# bus_filter.net
KiCad netlist of a schematic drawn in Altium Designer
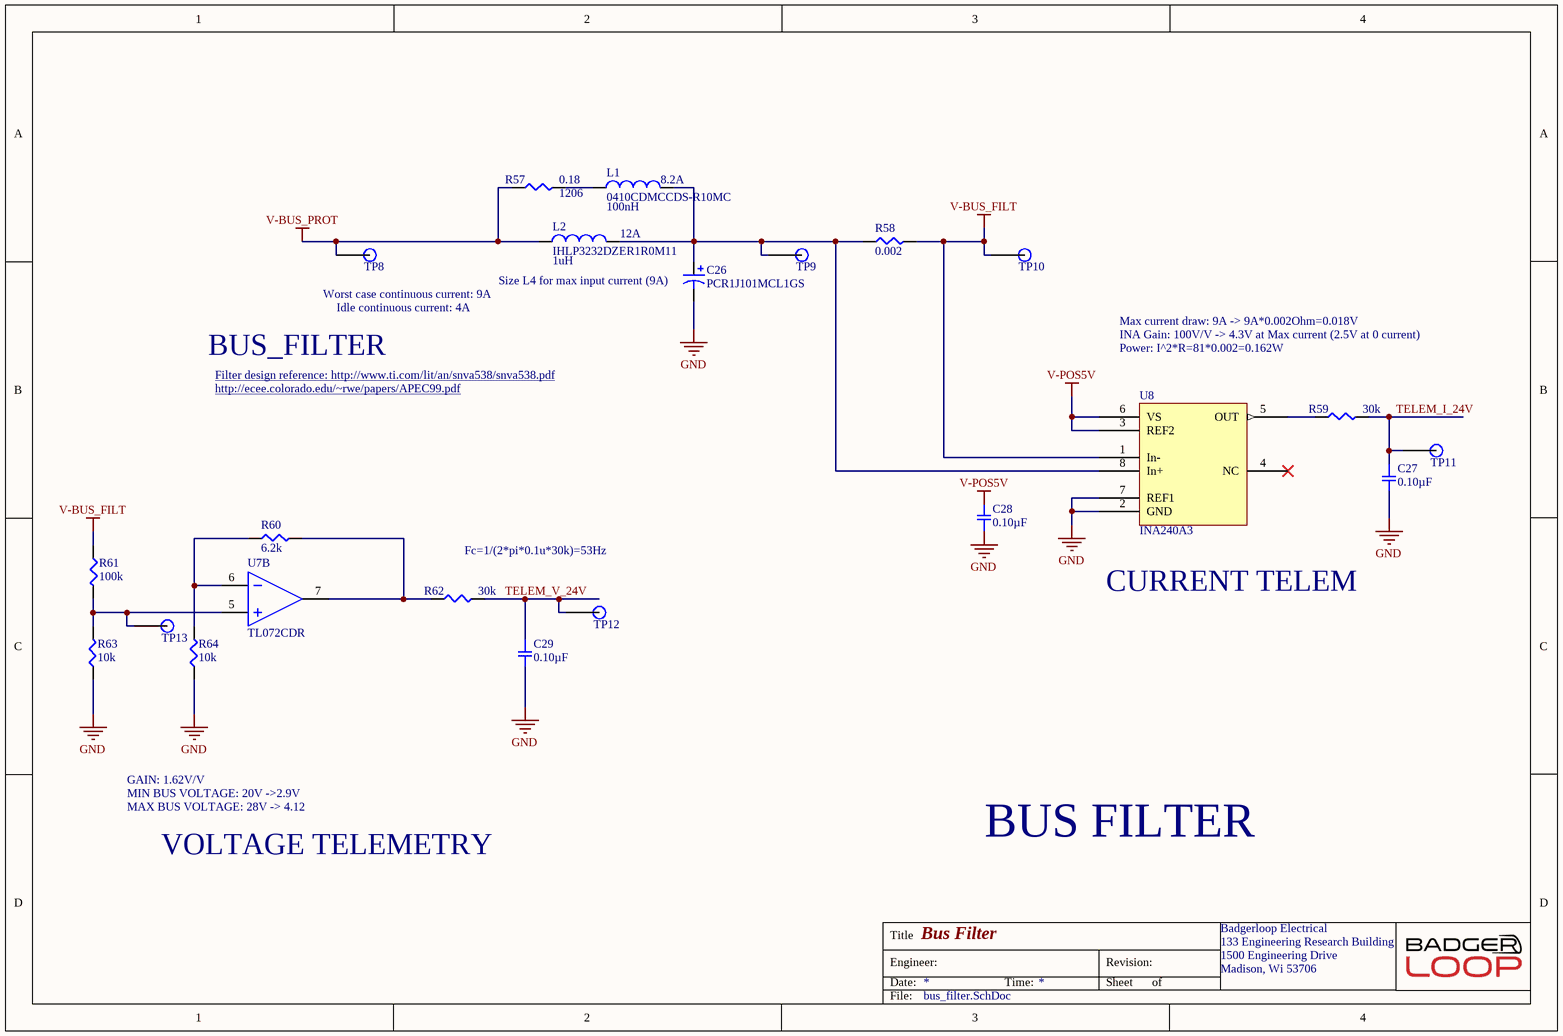
[diagram p0: bus_filter.SchDoc]

(export (version "E")
  (design (tool "Eeschema 10.0.6"))
  (components
    (comp (ref "C26")
      (value "PCR1J101MCL1GS")
      (footprint "CAPAE110103X126M")
      (description "CAP ALUM POLY 100UF 20% 63V SMD")
      (fields (field (name "MANUFACTURER") "Nichicon") (field (name "TOLERANCE") "20%"))
      (libsource (lib "capacitors") (part "PCR1J101MCL1GS"))
    )
    (comp (ref "C27")
      (value "0.10µF")
      (footprint "SMD-0805C")
      (description "CAP CER 0.1UF 16V X7R 0805")
      (fields
        (field (name "DIGI-KEY PART NUMBER") "490-1683-1-ND")
        (field (name "PART NUMBER") "GRM219R71C104KA01D")
      )
      (libsource (lib "capacitors") (part "GRM219R71C104KA01D"))
    )
    (comp (ref "C28")
      (value "0.10µF")
      (footprint "SMD-0805C")
      (description "CAP CER 0.1UF 10V U2J 0805")
      (fields
        (field (name "DIGI-KEY PART NUMBER") "490-11592-1-ND")
        (field (name "PART NUMBER") "GRM21B7U1A104JA01L")
      )
      (libsource (lib "capacitors") (part "GRM21B7U1A104JA01L"))
    )
    (comp (ref "C29")
      (value "0.10µF")
      (footprint "SMD-0805C")
      (description "CAP CER 0.1UF 16V X7R 0805")
      (fields
        (field (name "DIGI-KEY PART NUMBER") "490-1683-1-ND")
        (field (name "PART NUMBER") "GRM219R71C104KA01D")
      )
      (libsource (lib "capacitors") (part "GRM219R71C104KA01D"))
    )
    (comp (ref "L1")
      (value "0410CDMCCDS-R10MC")
      (footprint "INDM4442X20N")
      (fields
        (field (name "MANUFACTURER") "Sumida")
        (field (name "INDUCTANCE") "100nH")
        (field (name "SATURATION CURRENT") "8.2A")
      )
      (libsource (lib "inductor") (part "0410CDMCCDS-R10MC"))
    )
    (comp (ref "L2")
      (value "IHLP3232DZER1R0M11")
      (footprint "INDM8682X40N")
      (description "Fixed Inductors 1uH 20% Low Profile")
      (fields
        (field (name "MANUFACTURER") "Vishay Dale")
        (field (name "TOLERANCE") "20%")
        (field (name "SATURATION CURRENT") "12A")
        (field (name "INDUCTANCE") "1uH")
      )
      (libsource (lib "misc") (part "IHLP3232DZER1R0M11"))
    )
    (comp (ref "R57")
      (value "0.18")
      (footprint "SMD-1206-RES")
      (description "RES SMD 0.18 OHM 1% 1/2W 1206")
      (fields
        (field (name "PART NUMBER") "ERJ-8BSFR18V")
        (field (name "DIGI-KEY PART NUMBER") "P17683CT-ND")
        (field (name "SUPPLIER DEVICE PACKAGE") "1206")
      )
      (libsource (lib "resistors") (part "ERJ-8BSFR18V"))
    )
    (comp (ref "R58")
      (value "0.002")
      (footprint "SMD-1206-RES")
      (description "RES SMD 0.002 OHM 1% 1W 1206")
      (fields
        (field (name "PART NUMBER") "ERJ-MP2MF2M0U")
        (field (name "DIGI-KEY PART NUMBER") "P19341CT-ND")
      )
      (libsource (lib "resistors") (part "ERJ-MP2MF2M0U"))
    )
    (comp (ref "R59")
      (value "30k")
      (footprint "SMD-0805-RES")
      (description "RES SMD 30K OHM 1% 1/8W 0805")
      (fields
        (field (name "PART NUMBER") "ERJ-6ENF3002V")
        (field (name "DIGI-KEY PART NUMBER") "P30.0KCCT-ND")
      )
      (libsource (lib "resistors") (part "ERJ-6ENF3002V"))
    )
    (comp (ref "R60")
      (value "6.2k")
      (footprint "SMD-0805-RES")
      (description "RES SMD 6.2K OHM 5% 1/2W 0805")
      (fields
        (field (name "PART NUMBER") "ERJ-P06J622V")
        (field (name "DIGI-KEY PART NUMBER") "P6.2KADCT-ND")
      )
      (libsource (lib "resistors") (part "ERJ-P06J622V"))
    )
    (comp (ref "R61")
      (value "100k")
      (footprint "SMD-0805-RES")
      (description "RES SMD 100K OHM 5% 1/2W 0805")
      (fields
        (field (name "PART NUMBER") "ERJ-P06J104V")
        (field (name "DIGI-KEY PART NUMBER") "P100KADCT-ND")
      )
      (libsource (lib "resistors") (part "ERJ-P06J104V"))
    )
    (comp (ref "R62")
      (value "30k")
      (footprint "SMD-0805-RES")
      (description "RES SMD 30K OHM 1% 1/8W 0805")
      (fields
        (field (name "PART NUMBER") "ERJ-6ENF3002V")
        (field (name "DIGI-KEY PART NUMBER") "P30.0KCCT-ND")
      )
      (libsource (lib "resistors") (part "ERJ-6ENF3002V"))
    )
    (comp (ref "R63")
      (value "10k")
      (footprint "SMD-0805-RES")
      (description "RES SMD 10K OHM 5% 1/2W 0805")
      (fields (field (name "PART NUMBER") "ERJ-P06J103V") (field (name "DIGI-KEY PART NUMBER") "P10KADCT-ND"))
      (libsource (lib "resistors") (part "ERJ-P06J103V"))
    )
    (comp (ref "R64")
      (value "10k")
      (footprint "SMD-0805-RES")
      (description "RES SMD 10K OHM 5% 1/2W 0805")
      (fields (field (name "PART NUMBER") "ERJ-P06J103V") (field (name "DIGI-KEY PART NUMBER") "P10KADCT-ND"))
      (libsource (lib "resistors") (part "ERJ-P06J103V"))
    )
    (comp (ref "TP8")
      (value "TP")
      (footprint "Test Point")
      (description "SMD TEST POINT")
      (libsource (lib "misc") (part "TP"))
    )
    (comp (ref "TP9")
      (value "TP")
      (footprint "Test Point")
      (description "SMD TEST POINT")
      (libsource (lib "misc") (part "TP"))
    )
    (comp (ref "TP10")
      (value "TP")
      (footprint "Test Point")
      (description "SMD TEST POINT")
      (libsource (lib "misc") (part "TP"))
    )
    (comp (ref "TP11")
      (value "TP")
      (footprint "Test Point")
      (description "SMD TEST POINT")
      (libsource (lib "misc") (part "TP"))
    )
    (comp (ref "TP12")
      (value "TP")
      (footprint "Test Point")
      (description "SMD TEST POINT")
      (libsource (lib "misc") (part "TP"))
    )
    (comp (ref "TP13")
      (value "TP")
      (footprint "Test Point")
      (description "SMD TEST POINT")
      (libsource (lib "misc") (part "TP"))
    )
    (comp (ref "U7")
      (value "TL072CDR")
      (footprint "SOP127P600X175-8N")
      (description "IC OPAMP JFET 3MHZ 8SOIC")
      (fields (field (name "MANUFACTURER") "Texas Instruments"))
      (libsource (lib "ic") (part "TL072CDR"))
    )
    (comp (ref "U8")
      (value "INA240A3")
      (footprint "SOIC127P600X175-8N")
      (description "IC AMP CURRENT SENSE 8-TSSOP 100V/V")
      (fields (field (name "MANUFACTURER") "Texas Instruments"))
      (libsource (lib "ic") (part "INA240A3"))
    )
  )
  (nets
    (net (code "1") (name "/TELEM_I_24V") (class "Default")
      (node (ref "C27") (pin "1") (pinfunction "1_1") (pintype "passive"))
      (node (ref "R59") (pin "2") (pinfunction "2_2") (pintype "passive"))
      (node (ref "TP11") (pin "1") (pinfunction "1_1") (pintype "passive"))
    )
    (net (code "2") (name "/TELEM_V_24V") (class "Default")
      (node (ref "C29") (pin "1") (pinfunction "1_1") (pintype "passive"))
      (node (ref "R62") (pin "2") (pinfunction "2_2") (pintype "passive"))
      (node (ref "TP12") (pin "1") (pinfunction "1_1") (pintype "passive"))
    )
    (net (code "3") (name "GND") (class "Default")
      (node (ref "C26") (pin "2") (pinfunction "2_2") (pintype "passive"))
      (node (ref "C27") (pin "2") (pinfunction "2_2") (pintype "passive"))
      (node (ref "C28") (pin "1") (pinfunction "1_1") (pintype "passive"))
      (node (ref "C29") (pin "2") (pinfunction "2_2") (pintype "passive"))
      (node (ref "R63") (pin "1") (pinfunction "1_1") (pintype "passive"))
      (node (ref "R64") (pin "1") (pinfunction "1_1") (pintype "passive"))
      (node (ref "U8") (pin "2") (pinfunction "GND_2") (pintype "power_in"))
      (node (ref "U8") (pin "7") (pinfunction "REF1_7") (pintype "passive"))
    )
    (net (code "4") (name "Net-(L1-Pad1)") (class "Default")
      (node (ref "L1") (pin "1") (pinfunction "1_1") (pintype "passive"))
      (node (ref "R57") (pin "2") (pinfunction "2_2") (pintype "passive"))
    )
    (net (code "5") (name "Net-(U7B-IN+)") (class "Default")
      (node (ref "R61") (pin "2") (pinfunction "2_2") (pintype "passive"))
      (node (ref "R63") (pin "2") (pinfunction "2_2") (pintype "passive"))
      (node (ref "TP13") (pin "1") (pinfunction "1_1") (pintype "passive"))
      (node (ref "U7") (pin "5") (pinfunction "IN+_5") (pintype "passive"))
    )
    (net (code "6") (name "Net-(U7B-IN-)") (class "Default")
      (node (ref "R60") (pin "1") (pinfunction "1_1") (pintype "passive"))
      (node (ref "R64") (pin "2") (pinfunction "2_2") (pintype "passive"))
      (node (ref "U7") (pin "6") (pinfunction "IN-_6") (pintype "passive"))
    )
    (net (code "7") (name "Net-(U7B-OUT)") (class "Default")
      (node (ref "R60") (pin "2") (pinfunction "2_2") (pintype "passive"))
      (node (ref "R62") (pin "1") (pinfunction "1_1") (pintype "passive"))
      (node (ref "U7") (pin "7") (pinfunction "OUT_7") (pintype "passive"))
    )
    (net (code "8") (name "Net-(U8-In+)") (class "Default")
      (node (ref "C26") (pin "1") (pinfunction "1_1") (pintype "passive"))
      (node (ref "L1") (pin "2") (pinfunction "2_2") (pintype "passive"))
      (node (ref "L2") (pin "2") (pinfunction "2_2") (pintype "passive"))
      (node (ref "R58") (pin "1") (pinfunction "1_1") (pintype "passive"))
      (node (ref "TP9") (pin "1") (pinfunction "1_1") (pintype "passive"))
      (node (ref "U8") (pin "8") (pinfunction "In+_8") (pintype "passive"))
    )
    (net (code "9") (name "Net-(U8-OUT)") (class "Default")
      (node (ref "R59") (pin "1") (pinfunction "1_1") (pintype "passive"))
      (node (ref "U8") (pin "5") (pinfunction "OUT_5") (pintype "output"))
    )
    (net (code "10") (name "V-BUS_FILT") (class "Default")
      (node (ref "R58") (pin "2") (pinfunction "2_2") (pintype "passive"))
      (node (ref "R61") (pin "1") (pinfunction "1_1") (pintype "passive"))
      (node (ref "TP10") (pin "1") (pinfunction "1_1") (pintype "passive"))
      (node (ref "U8") (pin "1") (pinfunction "In-_1") (pintype "passive"))
    )
    (net (code "11") (name "V-BUS_PROT") (class "Default")
      (node (ref "L2") (pin "1") (pinfunction "1_1") (pintype "passive"))
      (node (ref "R57") (pin "1") (pinfunction "1_1") (pintype "passive"))
      (node (ref "TP8") (pin "1") (pinfunction "1_1") (pintype "passive"))
    )
    (net (code "12") (name "V-POS5V") (class "Default")
      (node (ref "C28") (pin "2") (pinfunction "2_2") (pintype "passive"))
      (node (ref "U8") (pin "3") (pinfunction "REF2_3") (pintype "passive"))
      (node (ref "U8") (pin "6") (pinfunction "VS_6") (pintype "power_in"))
    )
    (net (code "13") (name "unconnected-(U8-NC-Pad4)") (class "Default")
      (node (ref "U8") (pin "4") (pinfunction "NC_4") (pintype "passive+no_connect"))
    )
  )
)
